# LoRa.net
KiCad netlist of a schematic drawn in Altium Designer
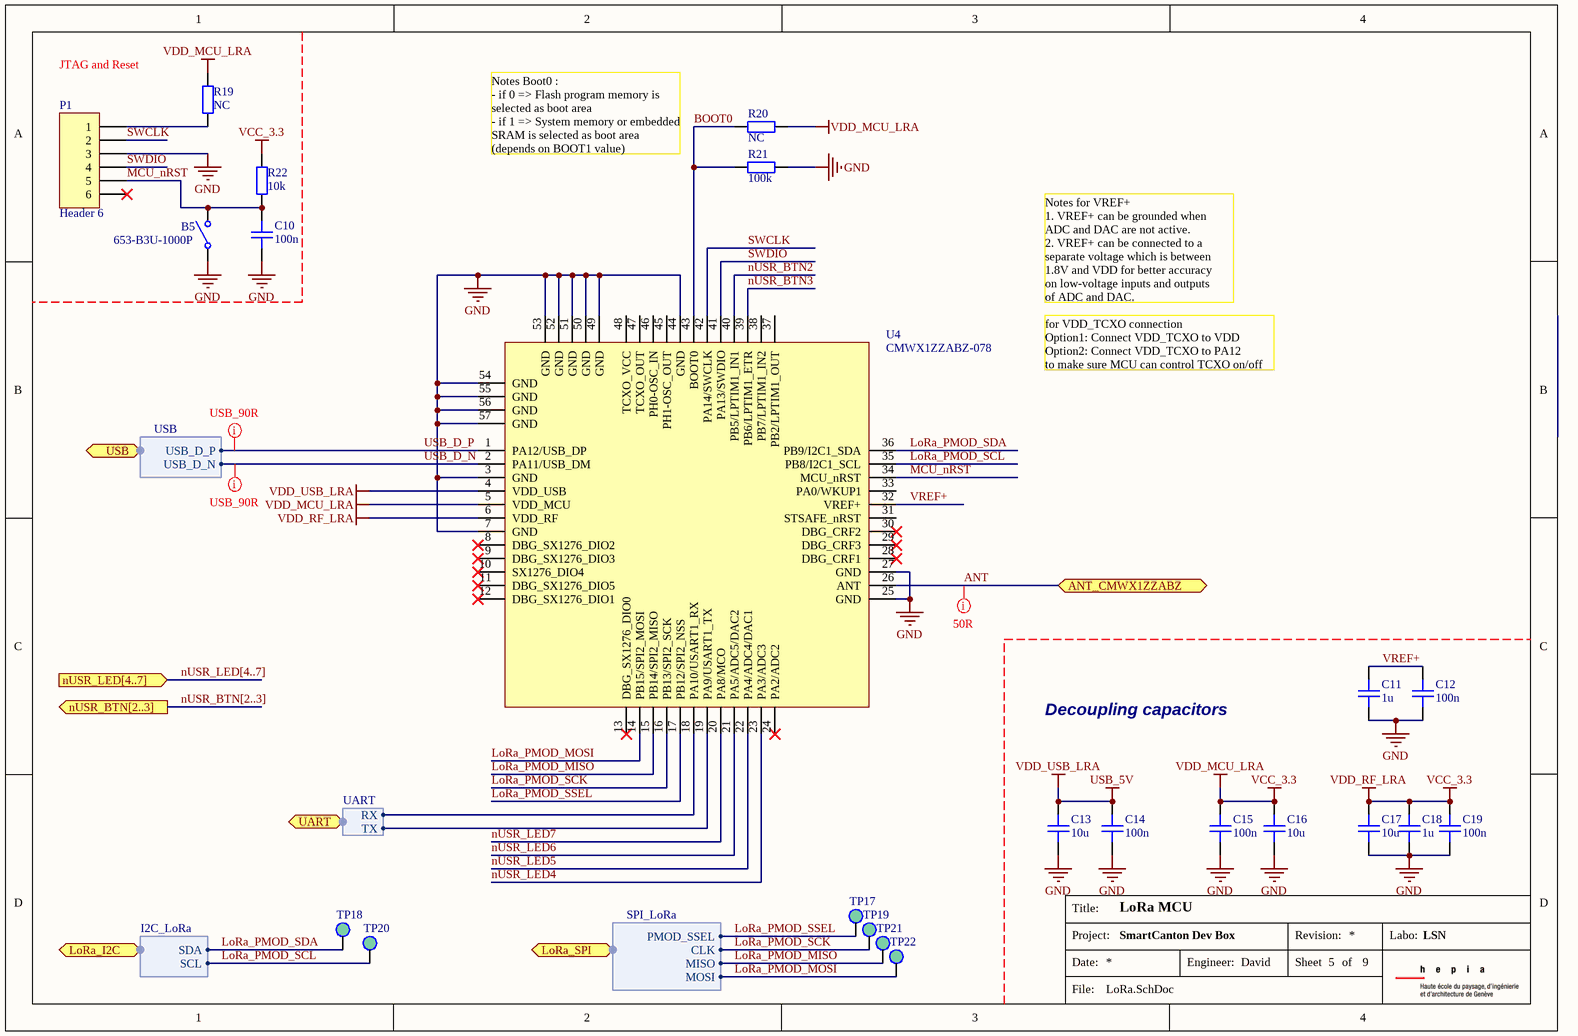
[diagram p0: LoRa.SchDoc]

(export (version "E")
  (design (tool "Eeschema 10.0.6"))
  (components
    (comp (ref "B5")
      (value "653-B3U-1000P")
      (footprint "B3U-1000P")
      (fields (field (name "SUPPLIER PART NUMBER 1") "653-B3U-1000P"))
      (libsource (lib "eSurf_handle") (part "PUSH_BUTTON"))
    )
    (comp (ref "C10")
      (value "100n")
      (footprint "CAPC1608X08")
      (description "MLCC Capacitor 1608")
      (libsource (lib "HEPIA Vault") (part "Capacitor"))
    )
    (comp (ref "C11")
      (value "1u")
      (footprint "CAPC1608X08N")
      (description "MLCC Capacitor 1608")
      (libsource (lib "HEPIA Vault") (part "CMP-001-0010-A.1"))
    )
    (comp (ref "C12")
      (value "100n")
      (footprint "CAPC1608X08N")
      (description "MLCC Capacitor 1608")
      (libsource (lib "HEPIA Vault") (part "CMP-001-0010-A.1"))
    )
    (comp (ref "C13")
      (value "10u")
      (footprint "CAPC1608X08N")
      (description "MLCC Capacitor 1608")
      (libsource (lib "HEPIA Vault") (part "CMP-001-0010-A.1"))
    )
    (comp (ref "C14")
      (value "100n")
      (footprint "CAPC1608X08N")
      (description "MLCC Capacitor 1608")
      (libsource (lib "HEPIA Vault") (part "CMP-001-0010-A.1"))
    )
    (comp (ref "C15")
      (value "100n")
      (footprint "CAPC1608X08N")
      (description "MLCC Capacitor 1608")
      (libsource (lib "HEPIA Vault") (part "CMP-001-0010-A.1"))
    )
    (comp (ref "C16")
      (value "10u")
      (footprint "CAPC1608X08N")
      (description "MLCC Capacitor 1608")
      (libsource (lib "HEPIA Vault") (part "CMP-001-0010-A.1"))
    )
    (comp (ref "C17")
      (value "10u")
      (footprint "CAPC1608X08N")
      (description "MLCC Capacitor 1608")
      (libsource (lib "HEPIA Vault") (part "CMP-001-0010-A.1"))
    )
    (comp (ref "C18")
      (value "1u")
      (footprint "CAPC1608X08N")
      (description "MLCC Capacitor 1608")
      (libsource (lib "HEPIA Vault") (part "CMP-001-0010-A.1"))
    )
    (comp (ref "C19")
      (value "100n")
      (footprint "CAPC1608X08N")
      (description "MLCC Capacitor 1608")
      (libsource (lib "HEPIA Vault") (part "CMP-001-0010-A.1"))
    )
    (comp (ref "P1")
      (value "Header 6")
      (footprint "HDR1X6")
      (description "Header, 6-Pin")
      (fields (field (name "PUBLISHER") "Altium Limited"))
      (libsource (lib "Miscellaneous Connectors") (part "Header 6"))
    )
    (comp (ref "R19")
      (value "NC")
      (footprint "RESC1608X06")
      (description "1608 resistor")
      (libsource (lib "HEPIA Vault") (part "CMP-001-0005-A.4"))
    )
    (comp (ref "R20")
      (value "NC")
      (footprint "RESC1608X06")
      (description "1608 resistor")
      (libsource (lib "") (part "CMP-001-0005-A.4_1"))
    )
    (comp (ref "R21")
      (value "100k")
      (footprint "RESC1608X06")
      (description "1608 resistor")
      (libsource (lib "") (part "CMP-001-0005-A.4_1"))
    )
    (comp (ref "R22")
      (value "10k")
      (footprint "RESC1608X06")
      (description "1608 resistor")
      (libsource (lib "HEPIA Vault") (part "CMP-001-0005-A.4"))
    )
    (comp (ref "TP17")
      (value "5015")
      (footprint "5015")
      (description "Circuit Board Hardware - PCB MINI SMT TEST POINT")
      (libsource (lib "HEPIA Vault") (part "CMP-001-0108-A.3"))
    )
    (comp (ref "TP18")
      (value "5015")
      (footprint "5015")
      (description "Circuit Board Hardware - PCB MINI SMT TEST POINT")
      (libsource (lib "HEPIA Vault") (part "CMP-001-0108-A.3"))
    )
    (comp (ref "TP19")
      (value "5015")
      (footprint "5015")
      (description "Circuit Board Hardware - PCB MINI SMT TEST POINT")
      (libsource (lib "HEPIA Vault") (part "CMP-001-0108-A.3"))
    )
    (comp (ref "TP20")
      (value "5015")
      (footprint "5015")
      (description "Circuit Board Hardware - PCB MINI SMT TEST POINT")
      (libsource (lib "HEPIA Vault") (part "CMP-001-0108-A.3"))
    )
    (comp (ref "TP21")
      (value "5015")
      (footprint "5015")
      (description "Circuit Board Hardware - PCB MINI SMT TEST POINT")
      (libsource (lib "HEPIA Vault") (part "CMP-001-0108-A.3"))
    )
    (comp (ref "TP22")
      (value "5015")
      (footprint "5015")
      (description "Circuit Board Hardware - PCB MINI SMT TEST POINT")
      (libsource (lib "HEPIA Vault") (part "CMP-001-0108-A.3"))
    )
    (comp (ref "U4")
      (value "CMWX1ZZABZ-078")
      (footprint "CMWX1ZZABZ-078")
      (description "RF Modules Type ABZ LoRa Module MCU - STM32L082")
      (libsource (lib "HEPIA Vault") (part "CMWX1ZZABZ"))
    )
  )
  (nets
    (net (code "5") (name "/ANT") (class "Default")
      (node (ref "U4") (pin "26") (pinfunction "ANT_26") (pintype "passive"))
    )
    (net (code "6") (name "/BOOT0") (class "Default")
      (node (ref "R20") (pin "1") (pinfunction "1_1") (pintype "passive"))
      (node (ref "R21") (pin "1") (pinfunction "1_1") (pintype "passive"))
      (node (ref "U4") (pin "43") (pinfunction "BOOT0_43") (pintype "passive"))
    )
    (net (code "7") (name "/LoRa_PMOD_MISO") (class "Default")
      (node (ref "TP21") (pin "1") (pinfunction "TP_1") (pintype "passive"))
      (node (ref "U4") (pin "15") (pinfunction "PB14/SPI2_MISO_15") (pintype "passive"))
    )
    (net (code "8") (name "/LoRa_PMOD_MOSI") (class "Default")
      (node (ref "TP22") (pin "1") (pinfunction "TP_1") (pintype "passive"))
      (node (ref "U4") (pin "14") (pinfunction "PB15/SPI2_MOSI_14") (pintype "passive"))
    )
    (net (code "9") (name "/LoRa_PMOD_SCK") (class "Default")
      (node (ref "TP19") (pin "1") (pinfunction "TP_1") (pintype "passive"))
      (node (ref "U4") (pin "16") (pinfunction "PB13/SPI2_SCK_16") (pintype "passive"))
    )
    (net (code "10") (name "/LoRa_PMOD_SCL") (class "Default")
      (node (ref "TP20") (pin "1") (pinfunction "TP_1") (pintype "passive"))
      (node (ref "U4") (pin "35") (pinfunction "PB8/I2C1_SCL_35") (pintype "passive"))
    )
    (net (code "11") (name "/LoRa_PMOD_SDA") (class "Default")
      (node (ref "TP18") (pin "1") (pinfunction "TP_1") (pintype "passive"))
      (node (ref "U4") (pin "36") (pinfunction "PB9/I2C1_SDA_36") (pintype "passive"))
    )
    (net (code "12") (name "/LoRa_PMOD_SSEL") (class "Default")
      (node (ref "TP17") (pin "1") (pinfunction "TP_1") (pintype "passive"))
      (node (ref "U4") (pin "17") (pinfunction "PB12/SPI2_NSS_17") (pintype "passive"))
    )
    (net (code "13") (name "/MCU_nRST") (class "Default")
      (node (ref "B5") (pin "2") (pinfunction "2_2") (pintype "passive"))
      (node (ref "C10") (pin "2") (pinfunction "2_2") (pintype "passive"))
      (node (ref "P1") (pin "5") (pinfunction "5_5") (pintype "passive"))
      (node (ref "R22") (pin "2") (pinfunction "2_2") (pintype "passive"))
      (node (ref "U4") (pin "34") (pinfunction "MCU_nRST_34") (pintype "passive"))
    )
    (net (code "14") (name "/RX") (class "Default")
      (node (ref "U4") (pin "18") (pinfunction "PA10/USART1_RX_18") (pintype "passive"))
    )
    (net (code "15") (name "/SWCLK") (class "Default")
      (node (ref "P1") (pin "2") (pinfunction "2_2") (pintype "passive"))
      (node (ref "U4") (pin "42") (pinfunction "PA14/SWCLK_42") (pintype "passive"))
    )
    (net (code "16") (name "/SWDIO") (class "Default")
      (node (ref "P1") (pin "4") (pinfunction "4_4") (pintype "passive"))
      (node (ref "U4") (pin "41") (pinfunction "PA13/SWDIO_41") (pintype "passive"))
    )
    (net (code "17") (name "/TX") (class "Default")
      (node (ref "U4") (pin "19") (pinfunction "PA9/USART1_TX_19") (pintype "passive"))
    )
    (net (code "18") (name "/USB_D_N") (class "Default")
      (node (ref "U4") (pin "2") (pinfunction "PA11/USB_DM_2") (pintype "passive"))
    )
    (net (code "19") (name "/USB_D_P") (class "Default")
      (node (ref "U4") (pin "1") (pinfunction "PA12/USB_DP_1") (pintype "passive"))
    )
    (net (code "20") (name "/VREF+") (class "Default")
      (node (ref "C11") (pin "2") (pinfunction "2_2") (pintype "passive"))
      (node (ref "C12") (pin "2") (pinfunction "2_2") (pintype "passive"))
      (node (ref "U4") (pin "32") (pinfunction "VREF+_32") (pintype "passive"))
    )
    (net (code "21") (name "/nUSR_BTN2") (class "Default")
      (node (ref "U4") (pin "40") (pinfunction "PB5/LPTIM1_IN1_40") (pintype "passive"))
    )
    (net (code "22") (name "/nUSR_BTN3") (class "Default")
      (node (ref "U4") (pin "39") (pinfunction "PB6/LPTIM1_ETR_39") (pintype "passive"))
    )
    (net (code "24") (name "/nUSR_LED4") (class "Default")
      (node (ref "U4") (pin "23") (pinfunction "PA3/ADC3_23") (pintype "passive"))
    )
    (net (code "25") (name "/nUSR_LED5") (class "Default")
      (node (ref "U4") (pin "22") (pinfunction "PA4/ADC4/DAC1_22") (pintype "passive"))
    )
    (net (code "26") (name "/nUSR_LED6") (class "Default")
      (node (ref "U4") (pin "21") (pinfunction "PA5/ADC5/DAC2_21") (pintype "passive"))
    )
    (net (code "27") (name "/nUSR_LED7") (class "Default")
      (node (ref "U4") (pin "20") (pinfunction "PA8/MCO_20") (pintype "passive"))
    )
    (net (code "33") (name "GND") (class "Default")
      (node (ref "B5") (pin "1") (pinfunction "1_1") (pintype "passive"))
      (node (ref "C10") (pin "1") (pinfunction "1_1") (pintype "passive"))
      (node (ref "C11") (pin "1") (pinfunction "1_1") (pintype "passive"))
      (node (ref "C12") (pin "1") (pinfunction "1_1") (pintype "passive"))
      (node (ref "C13") (pin "1") (pinfunction "1_1") (pintype "passive"))
      (node (ref "C14") (pin "1") (pinfunction "1_1") (pintype "passive"))
      (node (ref "C15") (pin "1") (pinfunction "1_1") (pintype "passive"))
      (node (ref "C16") (pin "1") (pinfunction "1_1") (pintype "passive"))
      (node (ref "C17") (pin "1") (pinfunction "1_1") (pintype "passive"))
      (node (ref "C18") (pin "1") (pinfunction "1_1") (pintype "passive"))
      (node (ref "C19") (pin "1") (pinfunction "1_1") (pintype "passive"))
      (node (ref "P1") (pin "3") (pinfunction "3_3") (pintype "passive"))
      (node (ref "R21") (pin "2") (pinfunction "2_2") (pintype "passive"))
      (node (ref "U4") (pin "25") (pinfunction "GND_25") (pintype "passive"))
      (node (ref "U4") (pin "27") (pinfunction "GND_27") (pintype "passive"))
      (node (ref "U4") (pin "3") (pinfunction "GND_3") (pintype "passive"))
      (node (ref "U4") (pin "44") (pinfunction "GND_44") (pintype "passive"))
      (node (ref "U4") (pin "49") (pinfunction "GND_49") (pintype "passive"))
      (node (ref "U4") (pin "50") (pinfunction "GND_50") (pintype "passive"))
      (node (ref "U4") (pin "51") (pinfunction "GND_51") (pintype "passive"))
      (node (ref "U4") (pin "52") (pinfunction "GND_52") (pintype "passive"))
      (node (ref "U4") (pin "53") (pinfunction "GND_53") (pintype "passive"))
      (node (ref "U4") (pin "54") (pinfunction "GND_54") (pintype "passive"))
      (node (ref "U4") (pin "55") (pinfunction "GND_55") (pintype "passive"))
      (node (ref "U4") (pin "56") (pinfunction "GND_56") (pintype "passive"))
      (node (ref "U4") (pin "57") (pinfunction "GND_57") (pintype "passive"))
      (node (ref "U4") (pin "7") (pinfunction "GND_7") (pintype "passive"))
    )
    (net (code "34") (name "Net-(P1-Pad1)") (class "Default")
      (node (ref "P1") (pin "1") (pinfunction "1_1") (pintype "passive"))
      (node (ref "R19") (pin "2") (pinfunction "2_2") (pintype "passive"))
    )
    (net (code "35") (name "USB_5V") (class "Default")
      (node (ref "C13") (pin "2") (pinfunction "2_2") (pintype "passive"))
      (node (ref "C14") (pin "2") (pinfunction "2_2") (pintype "passive"))
      (node (ref "U4") (pin "4") (pinfunction "VDD_USB_4") (pintype "passive"))
    )
    (net (code "36") (name "VCC_3.3") (class "Default")
      (node (ref "C15") (pin "2") (pinfunction "2_2") (pintype "passive"))
      (node (ref "C16") (pin "2") (pinfunction "2_2") (pintype "passive"))
      (node (ref "C17") (pin "2") (pinfunction "2_2") (pintype "passive"))
      (node (ref "C18") (pin "2") (pinfunction "2_2") (pintype "passive"))
      (node (ref "C19") (pin "2") (pinfunction "2_2") (pintype "passive"))
      (node (ref "R19") (pin "1") (pinfunction "1_1") (pintype "passive"))
      (node (ref "R20") (pin "2") (pinfunction "2_2") (pintype "passive"))
      (node (ref "R22") (pin "1") (pinfunction "1_1") (pintype "passive"))
      (node (ref "U4") (pin "5") (pinfunction "VDD_MCU_5") (pintype "passive"))
      (node (ref "U4") (pin "6") (pinfunction "VDD_RF_6") (pintype "passive"))
    )
    (net (code "37") (name "unconnected-(P1-Pad6)") (class "Default")
      (node (ref "P1") (pin "6") (pinfunction "6_6") (pintype "passive+no_connect"))
    )
    (net (code "38") (name "unconnected-(U4-DBG_CRF1-Pad28)") (class "Default")
      (node (ref "U4") (pin "28") (pinfunction "DBG_CRF1_28") (pintype "passive+no_connect"))
    )
    (net (code "39") (name "unconnected-(U4-DBG_CRF2-Pad30)") (class "Default")
      (node (ref "U4") (pin "30") (pinfunction "DBG_CRF2_30") (pintype "passive+no_connect"))
    )
    (net (code "40") (name "unconnected-(U4-DBG_CRF3-Pad29)") (class "Default")
      (node (ref "U4") (pin "29") (pinfunction "DBG_CRF3_29") (pintype "passive+no_connect"))
    )
    (net (code "41") (name "unconnected-(U4-DBG_SX1276_DIO0-Pad13)") (class "Default")
      (node (ref "U4") (pin "13") (pinfunction "DBG_SX1276_DIO0_13") (pintype "passive+no_connect"))
    )
    (net (code "42") (name "unconnected-(U4-DBG_SX1276_DIO1-Pad12)") (class "Default")
      (node (ref "U4") (pin "12") (pinfunction "DBG_SX1276_DIO1_12") (pintype "passive+no_connect"))
    )
    (net (code "43") (name "unconnected-(U4-DBG_SX1276_DIO2-Pad8)") (class "Default")
      (node (ref "U4") (pin "8") (pinfunction "DBG_SX1276_DIO2_8") (pintype "passive+no_connect"))
    )
    (net (code "44") (name "unconnected-(U4-DBG_SX1276_DIO3-Pad9)") (class "Default")
      (node (ref "U4") (pin "9") (pinfunction "DBG_SX1276_DIO3_9") (pintype "passive+no_connect"))
    )
    (net (code "45") (name "unconnected-(U4-DBG_SX1276_DIO5-Pad11)") (class "Default")
      (node (ref "U4") (pin "11") (pinfunction "DBG_SX1276_DIO5_11") (pintype "passive+no_connect"))
    )
    (net (code "46") (name "unconnected-(U4-PA0{slash}WKUP1-Pad33)") (class "Default")
      (node (ref "U4") (pin "33") (pinfunction "PA0/WKUP1_33") (pintype "passive"))
    )
    (net (code "47") (name "unconnected-(U4-PA2{slash}ADC2-Pad24)") (class "Default")
      (node (ref "U4") (pin "24") (pinfunction "PA2/ADC2_24") (pintype "passive+no_connect"))
    )
    (net (code "48") (name "unconnected-(U4-PB2{slash}LPTIM1_OUT-Pad37)") (class "Default")
      (node (ref "U4") (pin "37") (pinfunction "PB2/LPTIM1_OUT_37") (pintype "passive"))
    )
    (net (code "49") (name "unconnected-(U4-PB7{slash}LPTIM1_IN2-Pad38)") (class "Default")
      (node (ref "U4") (pin "38") (pinfunction "PB7/LPTIM1_IN2_38") (pintype "passive"))
    )
    (net (code "50") (name "unconnected-(U4-PH0-OSC_IN-Pad46)") (class "Default")
      (node (ref "U4") (pin "46") (pinfunction "PH0-OSC_IN_46") (pintype "passive"))
    )
    (net (code "51") (name "unconnected-(U4-PH1-OSC_OUT-Pad45)") (class "Default")
      (node (ref "U4") (pin "45") (pinfunction "PH1-OSC_OUT_45") (pintype "passive"))
    )
    (net (code "52") (name "unconnected-(U4-STSAFE_nRST-Pad31)") (class "Default")
      (node (ref "U4") (pin "31") (pinfunction "STSAFE_nRST_31") (pintype "passive"))
    )
    (net (code "53") (name "unconnected-(U4-SX1276_DIO4-Pad10)") (class "Default")
      (node (ref "U4") (pin "10") (pinfunction "SX1276_DIO4_10") (pintype "passive+no_connect"))
    )
    (net (code "54") (name "unconnected-(U4-TCXO_OUT-Pad47)") (class "Default")
      (node (ref "U4") (pin "47") (pinfunction "TCXO_OUT_47") (pintype "passive"))
    )
    (net (code "55") (name "unconnected-(U4-TCXO_VCC-Pad48)") (class "Default")
      (node (ref "U4") (pin "48") (pinfunction "TCXO_VCC_48") (pintype "passive"))
    )
  )
)
